# LEDS.net
KiCad netlist of a schematic drawn in Altium Designer
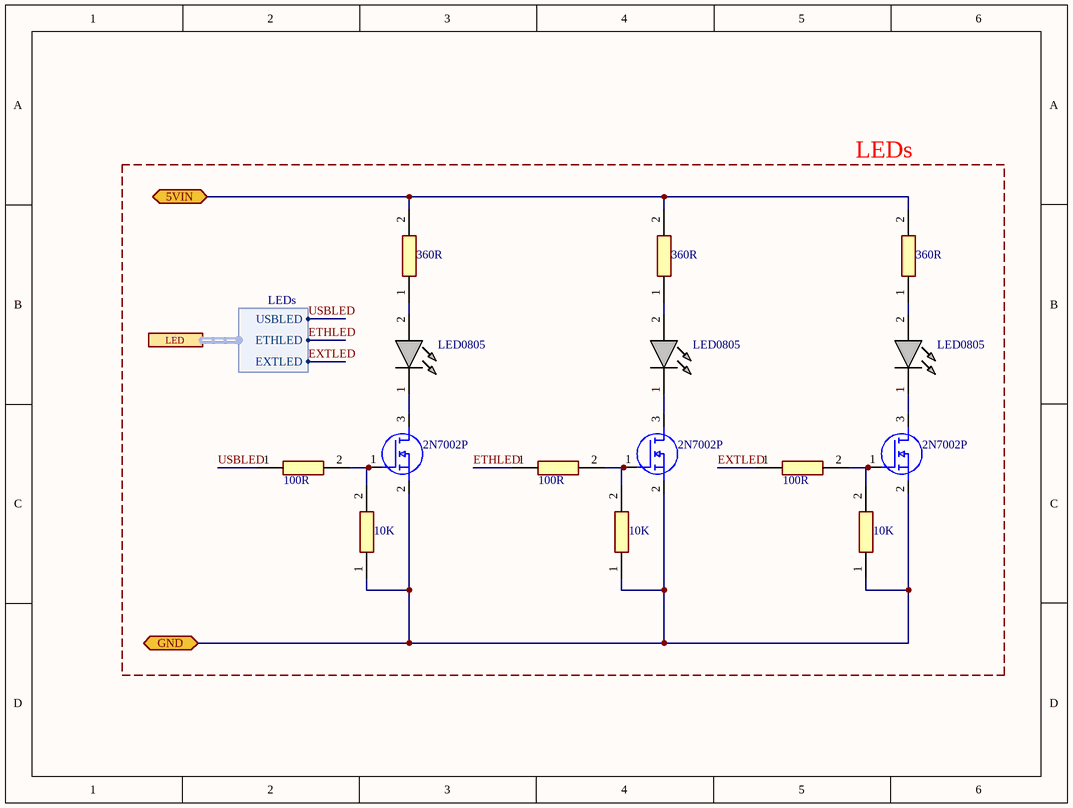
[diagram p0: LEDS.SchDoc]

(export (version "E")
  (design (tool "Eeschema 10.0.6"))
  (components
    (comp (ref "LEDETH(BLUE)")
      (value "LED0805")
      (footprint "LED0805")
      (description "LED-SMD0805")
      (libsource (lib "Components_Robots") (part "LED0805"))
    )
    (comp (ref "LEDEXT(YELLOW)")
      (value "LED0805")
      (footprint "LED0805")
      (description "LED-SMD0805")
      (libsource (lib "Components_Robots") (part "LED0805"))
    )
    (comp (ref "LEDUSB(BLUE)")
      (value "LED0805")
      (footprint "LED0805")
      (description "LED-SMD0805")
      (libsource (lib "Components_Robots") (part "LED0805"))
    )
    (comp (ref "NMOSETH")
      (value "2N7002P")
      (footprint "2N7002P")
      (description "2N7002P,215")
      (libsource (lib "Components_Robots") (part "2N7002P"))
    )
    (comp (ref "NMOSEXT")
      (value "2N7002P")
      (footprint "2N7002P")
      (description "2N7002P,215")
      (libsource (lib "Components_Robots") (part "2N7002P"))
    )
    (comp (ref "NMOSUSB")
      (value "2N7002P")
      (footprint "2N7002P")
      (description "2N7002P,215")
      (libsource (lib "Components_Robots") (part "2N7002P"))
    )
    (comp (ref "RESETH")
      (value "360R")
      (footprint "RES0805")
      (description "RES-SMD0805")
      (libsource (lib "Components_Robots") (part "RES0805"))
    )
    (comp (ref "RESEXT")
      (value "360R")
      (footprint "RES0805")
      (description "RES-SMD0805")
      (libsource (lib "Components_Robots") (part "RES0805"))
    )
    (comp (ref "RESG1")
      (value "100R")
      (footprint "RES0805")
      (description "RES-SMD0805")
      (libsource (lib "") (part "RES0805_1"))
    )
    (comp (ref "RESG2")
      (value "10K")
      (footprint "RES0805")
      (description "RES-SMD0805")
      (libsource (lib "Components_Robots") (part "RES0805"))
    )
    (comp (ref "RESG3")
      (value "100R")
      (footprint "RES0805")
      (description "RES-SMD0805")
      (libsource (lib "") (part "RES0805_1"))
    )
    (comp (ref "RESG4")
      (value "10K")
      (footprint "RES0805")
      (description "RES-SMD0805")
      (libsource (lib "Components_Robots") (part "RES0805"))
    )
    (comp (ref "RESG5")
      (value "100R")
      (footprint "RES0805")
      (description "RES-SMD0805")
      (libsource (lib "") (part "RES0805_1"))
    )
    (comp (ref "RESG6")
      (value "10K")
      (footprint "RES0805")
      (description "RES-SMD0805")
      (libsource (lib "Components_Robots") (part "RES0805"))
    )
    (comp (ref "RESUSB")
      (value "360R")
      (footprint "RES0805")
      (description "RES-SMD0805")
      (libsource (lib "Components_Robots") (part "RES0805"))
    )
  )
  (nets
    (net (code "2") (name "/5VIN") (class "Default")
      (node (ref "RESETH") (pin "2") (pinfunction "2_2") (pintype "passive"))
      (node (ref "RESEXT") (pin "2") (pinfunction "2_2") (pintype "passive"))
      (node (ref "RESUSB") (pin "2") (pinfunction "2_2") (pintype "passive"))
    )
    (net (code "3") (name "/ETHLED") (class "Default")
      (node (ref "RESG3") (pin "1") (pinfunction "1_1") (pintype "passive"))
    )
    (net (code "4") (name "/EXTLED") (class "Default")
      (node (ref "RESG5") (pin "1") (pinfunction "1_1") (pintype "passive"))
    )
    (net (code "5") (name "/GND") (class "Default")
      (node (ref "NMOSETH") (pin "2") (pinfunction "S_2") (pintype "passive"))
      (node (ref "NMOSEXT") (pin "2") (pinfunction "S_2") (pintype "passive"))
      (node (ref "NMOSUSB") (pin "2") (pinfunction "S_2") (pintype "passive"))
      (node (ref "RESG2") (pin "1") (pinfunction "1_1") (pintype "passive"))
      (node (ref "RESG4") (pin "1") (pinfunction "1_1") (pintype "passive"))
      (node (ref "RESG6") (pin "1") (pinfunction "1_1") (pintype "passive"))
    )
    (net (code "6") (name "/USBLED") (class "Default")
      (node (ref "RESG1") (pin "1") (pinfunction "1_1") (pintype "passive"))
    )
    (net (code "8") (name "Net-(LEDETH(BLUE)-A)") (class "Default")
      (node (ref "LEDETH(BLUE)") (pin "2") (pinfunction "A_2") (pintype "passive"))
      (node (ref "RESETH") (pin "1") (pinfunction "1_1") (pintype "passive"))
    )
    (net (code "9") (name "Net-(LEDETH(BLUE)-K)") (class "Default")
      (node (ref "LEDETH(BLUE)") (pin "1") (pinfunction "K_1") (pintype "passive"))
      (node (ref "NMOSETH") (pin "3") (pinfunction "D_3") (pintype "passive"))
    )
    (net (code "10") (name "Net-(LEDEXT(YELLOW)-A)") (class "Default")
      (node (ref "LEDEXT(YELLOW)") (pin "2") (pinfunction "A_2") (pintype "passive"))
      (node (ref "RESEXT") (pin "1") (pinfunction "1_1") (pintype "passive"))
    )
    (net (code "11") (name "Net-(LEDEXT(YELLOW)-K)") (class "Default")
      (node (ref "LEDEXT(YELLOW)") (pin "1") (pinfunction "K_1") (pintype "passive"))
      (node (ref "NMOSEXT") (pin "3") (pinfunction "D_3") (pintype "passive"))
    )
    (net (code "12") (name "Net-(LEDUSB(BLUE)-A)") (class "Default")
      (node (ref "LEDUSB(BLUE)") (pin "2") (pinfunction "A_2") (pintype "passive"))
      (node (ref "RESUSB") (pin "1") (pinfunction "1_1") (pintype "passive"))
    )
    (net (code "13") (name "Net-(LEDUSB(BLUE)-K)") (class "Default")
      (node (ref "LEDUSB(BLUE)") (pin "1") (pinfunction "K_1") (pintype "passive"))
      (node (ref "NMOSUSB") (pin "3") (pinfunction "D_3") (pintype "passive"))
    )
    (net (code "14") (name "Net-(NMOSETH-G)") (class "Default")
      (node (ref "NMOSETH") (pin "1") (pinfunction "G_1") (pintype "passive"))
      (node (ref "RESG3") (pin "2") (pinfunction "2_2") (pintype "passive"))
      (node (ref "RESG4") (pin "2") (pinfunction "2_2") (pintype "passive"))
    )
    (net (code "15") (name "Net-(NMOSEXT-G)") (class "Default")
      (node (ref "NMOSEXT") (pin "1") (pinfunction "G_1") (pintype "passive"))
      (node (ref "RESG5") (pin "2") (pinfunction "2_2") (pintype "passive"))
      (node (ref "RESG6") (pin "2") (pinfunction "2_2") (pintype "passive"))
    )
    (net (code "16") (name "Net-(NMOSUSB-G)") (class "Default")
      (node (ref "NMOSUSB") (pin "1") (pinfunction "G_1") (pintype "passive"))
      (node (ref "RESG1") (pin "2") (pinfunction "2_2") (pintype "passive"))
      (node (ref "RESG2") (pin "2") (pinfunction "2_2") (pintype "passive"))
    )
  )
)
